# companion_revc.net
KiCad netlist of a schematic drawn in EAGLE
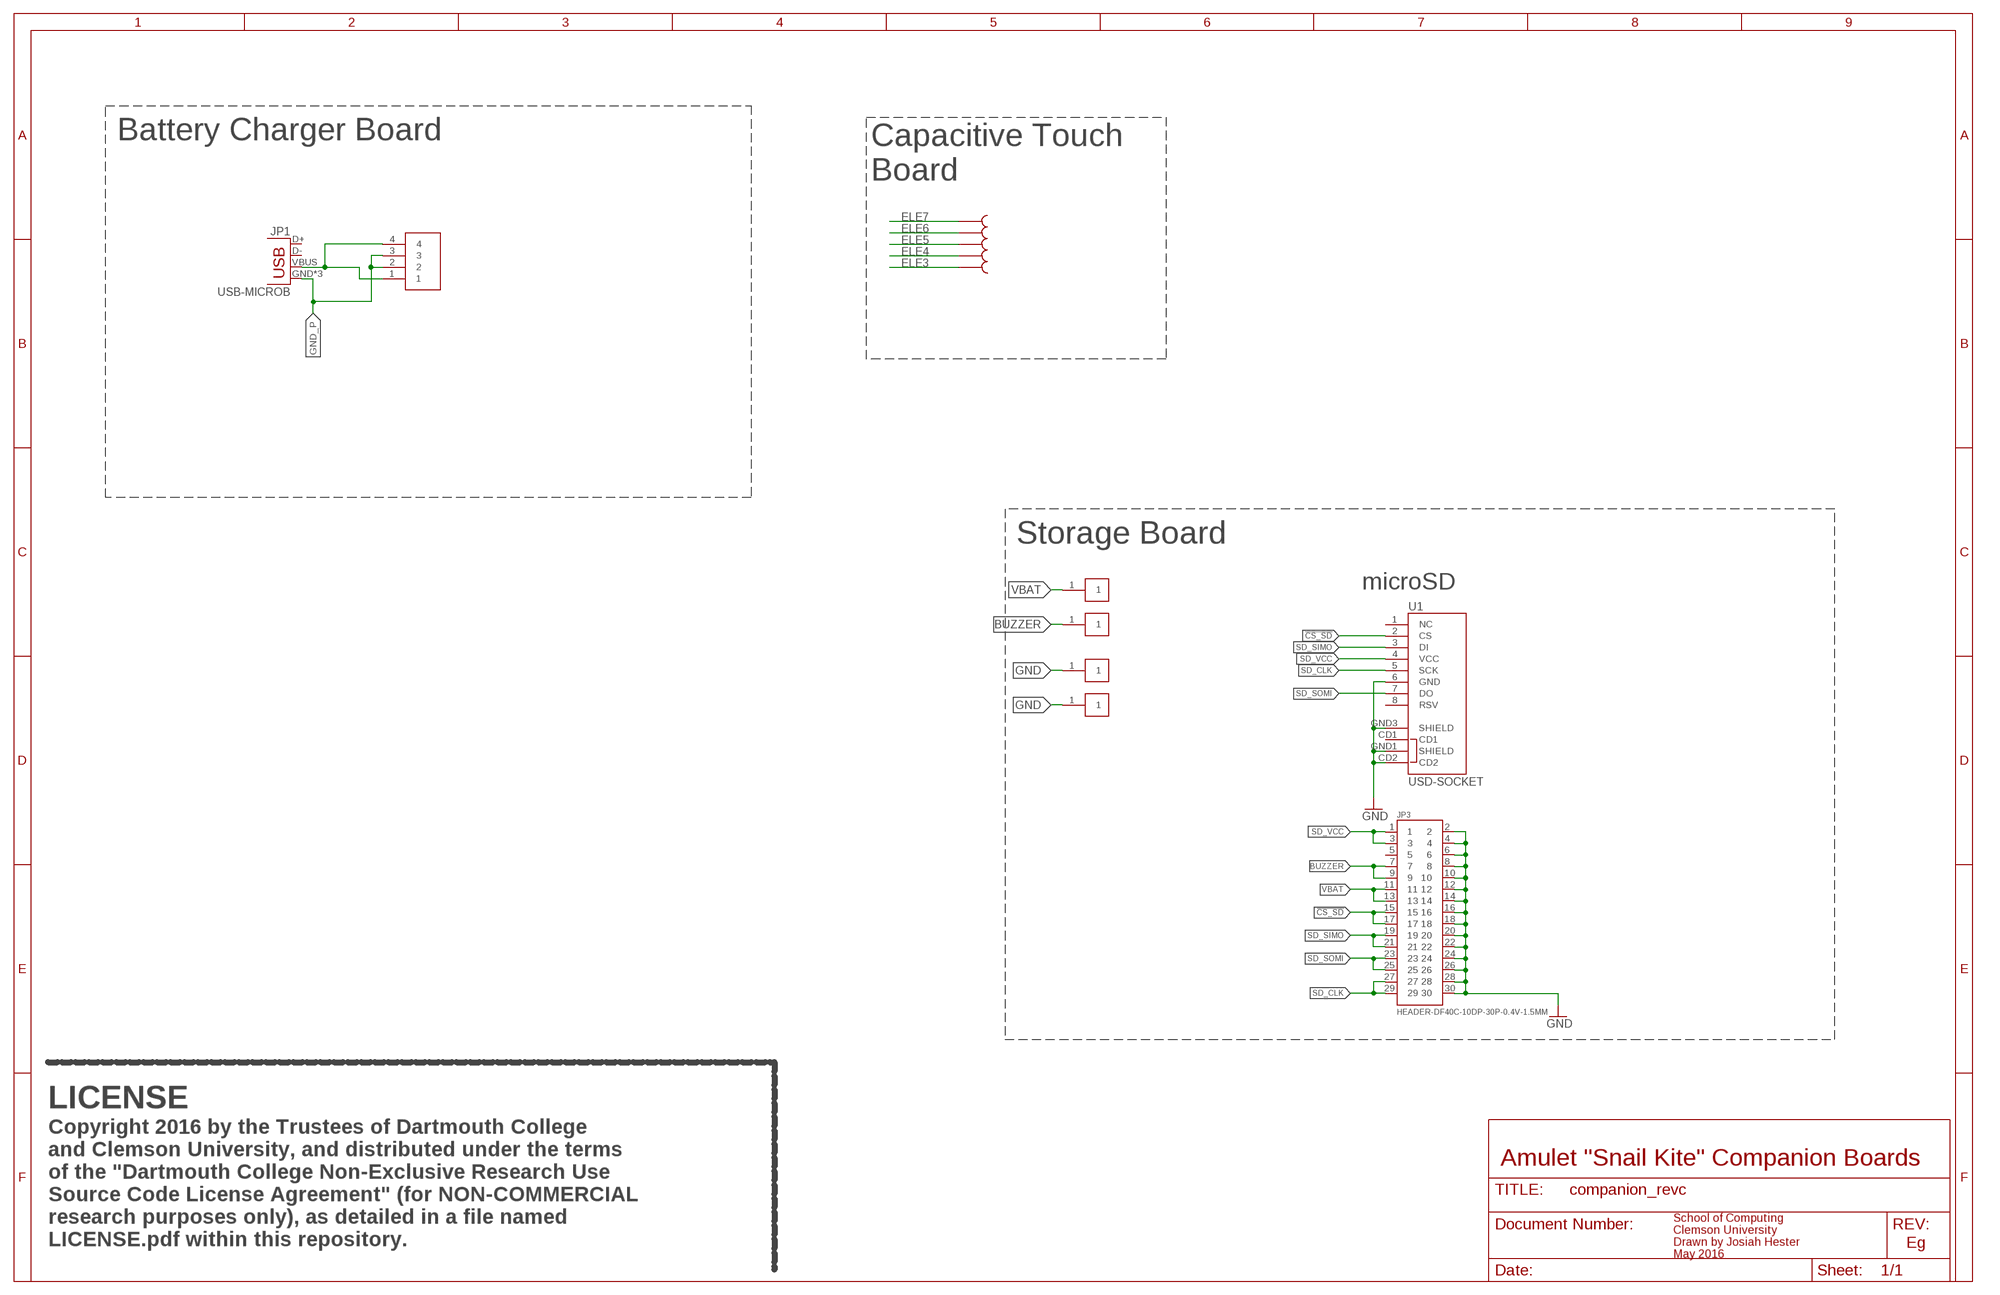
[diagram p0: schematic, sheet 1]

(export (version "E")
  (design (tool "Eeschema 10.0.6"))
  (components
    (comp (ref "JP1")
      (value "USB-MICROB")
      (footprint "eagle-import:USB-MICROB")
      (libsource (lib "eagle-import") (part "USB-MICROB"))
    )
    (comp (ref "JP3")
      (value "HEADER-DF40C-10DP-30P-0.4V-1.5MM")
      (footprint "eagle-import:HEADER-DF40-30")
      (libsource (lib "eagle-import") (part "HEADER-DF40C-10DP-30P-0.4V-1.5MM"))
    )
    (comp (ref "U$1")
      (value "CTPAD")
      (footprint "eagle-import:CTPAD")
      (libsource (lib "eagle-import") (part "CTPAD"))
    )
    (comp (ref "U$2")
      (value "CTPAD")
      (footprint "eagle-import:CTPAD")
      (libsource (lib "eagle-import") (part "CTPAD"))
    )
    (comp (ref "U$3")
      (value "CTPAD")
      (footprint "eagle-import:CTPAD")
      (libsource (lib "eagle-import") (part "CTPAD"))
    )
    (comp (ref "U$4")
      (value "CTPAD")
      (footprint "eagle-import:CTPAD")
      (libsource (lib "eagle-import") (part "CTPAD"))
    )
    (comp (ref "U$5")
      (value "CTPAD")
      (footprint "eagle-import:CTPAD")
      (libsource (lib "eagle-import") (part "CTPAD"))
    )
    (comp (ref "U$6")
      (value "1PAD")
      (footprint "eagle-import:5X23MM_PAD")
      (libsource (lib "eagle-import") (part "1PAD"))
    )
    (comp (ref "U$7")
      (value "1PAD")
      (footprint "eagle-import:5X23MM_PAD")
      (libsource (lib "eagle-import") (part "1PAD"))
    )
    (comp (ref "U$8")
      (value "1PAD")
      (footprint "eagle-import:5X23MM_PAD")
      (libsource (lib "eagle-import") (part "1PAD"))
    )
    (comp (ref "U$9")
      (value "1PAD")
      (footprint "eagle-import:5X23MM_PAD")
      (libsource (lib "eagle-import") (part "1PAD"))
    )
    (comp (ref "U$10")
      (value "1.27MM-MILLMAX")
      (footprint "eagle-import:1X03-1.27MM")
      (libsource (lib "eagle-import") (part "1.27MM-MILLMAX"))
    )
    (comp (ref "U1")
      (value "USD-SOCKET")
      (footprint "eagle-import:MICROSD_1_1")
      (libsource (lib "eagle-import") (part "USD-SOCKET"))
    )
  )
  (nets
    (net (code "1") (name "/ELE3") (class "Default")
      (node (ref "U$5") (pin "P$1") (pinfunction "P$1_P$1") (pintype "bidirectional"))
    )
    (net (code "2") (name "/ELE4") (class "Default")
      (node (ref "U$4") (pin "P$1") (pinfunction "P$1_P$1") (pintype "bidirectional"))
    )
    (net (code "3") (name "/ELE5") (class "Default")
      (node (ref "U$3") (pin "P$1") (pinfunction "P$1_P$1") (pintype "bidirectional"))
    )
    (net (code "4") (name "/ELE6") (class "Default")
      (node (ref "U$2") (pin "P$1") (pinfunction "P$1_P$1") (pintype "bidirectional"))
    )
    (net (code "5") (name "/ELE7") (class "Default")
      (node (ref "U$1") (pin "P$1") (pinfunction "P$1_P$1") (pintype "bidirectional"))
    )
    (net (code "6") (name "/~{CS_SD}") (class "Default")
      (node (ref "JP3") (pin "15") (pinfunction "15_15") (pintype "bidirectional"))
      (node (ref "JP3") (pin "17") (pinfunction "17_17") (pintype "bidirectional"))
      (node (ref "U1") (pin "2") (pinfunction "CS_2") (pintype "bidirectional"))
    )
    (net (code "7") (name "BUZZER") (class "Default")
      (node (ref "JP3") (pin "7") (pinfunction "7_7") (pintype "bidirectional"))
      (node (ref "JP3") (pin "9") (pinfunction "9_9") (pintype "bidirectional"))
      (node (ref "U$7") (pin "1") (pinfunction "1_1") (pintype "bidirectional"))
    )
    (net (code "8") (name "GND") (class "Default")
      (node (ref "JP3") (pin "10") (pinfunction "10_10") (pintype "bidirectional"))
      (node (ref "JP3") (pin "12") (pinfunction "12_12") (pintype "bidirectional"))
      (node (ref "JP3") (pin "14") (pinfunction "14_14") (pintype "bidirectional"))
      (node (ref "JP3") (pin "16") (pinfunction "16_16") (pintype "bidirectional"))
      (node (ref "JP3") (pin "18") (pinfunction "18_18") (pintype "bidirectional"))
      (node (ref "JP3") (pin "2") (pinfunction "2_2") (pintype "bidirectional"))
      (node (ref "JP3") (pin "20") (pinfunction "20_20") (pintype "bidirectional"))
      (node (ref "JP3") (pin "22") (pinfunction "22_22") (pintype "bidirectional"))
      (node (ref "JP3") (pin "24") (pinfunction "24_24") (pintype "bidirectional"))
      (node (ref "JP3") (pin "26") (pinfunction "26_26") (pintype "bidirectional"))
      (node (ref "JP3") (pin "28") (pinfunction "28_28") (pintype "bidirectional"))
      (node (ref "JP3") (pin "30") (pinfunction "30_30") (pintype "bidirectional"))
      (node (ref "JP3") (pin "4") (pinfunction "4_4") (pintype "bidirectional"))
      (node (ref "JP3") (pin "6") (pinfunction "6_6") (pintype "bidirectional"))
      (node (ref "JP3") (pin "8") (pinfunction "8_8") (pintype "bidirectional"))
      (node (ref "U$8") (pin "1") (pinfunction "1_1") (pintype "bidirectional"))
      (node (ref "U$9") (pin "1") (pinfunction "1_1") (pintype "bidirectional"))
      (node (ref "U1") (pin "6") (pinfunction "GND_6") (pintype "bidirectional"))
      (node (ref "U1") (pin "CD2") (pinfunction "CD2_CD2") (pintype "bidirectional"))
      (node (ref "U1") (pin "GND1") (pinfunction "SHIELD_GND1") (pintype "bidirectional"))
      (node (ref "U1") (pin "GND3") (pinfunction "SHIELD_GND3") (pintype "bidirectional"))
    )
    (net (code "9") (name "GND_P") (class "Default")
      (node (ref "JP1") (pin "GND") (pinfunction "GND_GND") (pintype "bidirectional"))
      (node (ref "JP1") (pin "MT1") (pinfunction "GND_MT1") (pintype "bidirectional"))
      (node (ref "JP1") (pin "MT2") (pinfunction "GND_MT2") (pintype "bidirectional"))
      (node (ref "U$10") (pin "2") (pinfunction "2_2") (pintype "bidirectional"))
      (node (ref "U$10") (pin "3") (pinfunction "3_3") (pintype "bidirectional"))
    )
    (net (code "10") (name "Net-(JP1-PadVBUS)") (class "Default")
      (node (ref "JP1") (pin "VBUS") (pinfunction "VBUS_VBUS") (pintype "bidirectional"))
      (node (ref "U$10") (pin "1") (pinfunction "1_1") (pintype "bidirectional"))
      (node (ref "U$10") (pin "4") (pinfunction "4_4") (pintype "bidirectional"))
    )
    (net (code "11") (name "SD_CLK") (class "Default")
      (node (ref "JP3") (pin "27") (pinfunction "27_27") (pintype "bidirectional"))
      (node (ref "JP3") (pin "29") (pinfunction "29_29") (pintype "bidirectional"))
      (node (ref "U1") (pin "5") (pinfunction "SCK_5") (pintype "bidirectional"))
    )
    (net (code "12") (name "SD_SIMO") (class "Default")
      (node (ref "JP3") (pin "19") (pinfunction "19_19") (pintype "bidirectional"))
      (node (ref "JP3") (pin "21") (pinfunction "21_21") (pintype "bidirectional"))
      (node (ref "U1") (pin "3") (pinfunction "DI_3") (pintype "bidirectional"))
    )
    (net (code "13") (name "SD_SOMI") (class "Default")
      (node (ref "JP3") (pin "23") (pinfunction "23_23") (pintype "bidirectional"))
      (node (ref "JP3") (pin "25") (pinfunction "25_25") (pintype "bidirectional"))
      (node (ref "U1") (pin "7") (pinfunction "DO_7") (pintype "bidirectional"))
    )
    (net (code "14") (name "SD_VCC") (class "Default")
      (node (ref "JP3") (pin "1") (pinfunction "1_1") (pintype "bidirectional"))
      (node (ref "JP3") (pin "3") (pinfunction "3_3") (pintype "bidirectional"))
      (node (ref "U1") (pin "4") (pinfunction "VCC_4") (pintype "bidirectional"))
    )
    (net (code "15") (name "VBAT") (class "Default")
      (node (ref "JP3") (pin "11") (pinfunction "11_11") (pintype "bidirectional"))
      (node (ref "JP3") (pin "13") (pinfunction "13_13") (pintype "bidirectional"))
      (node (ref "U$6") (pin "1") (pinfunction "1_1") (pintype "bidirectional"))
    )
    (net (code "16") (name "unconnected-(JP1-PadD+)") (class "Default")
      (node (ref "JP1") (pin "D+") (pinfunction "D+_D+") (pintype "bidirectional"))
    )
    (net (code "17") (name "unconnected-(JP1-PadD-)") (class "Default")
      (node (ref "JP1") (pin "D-") (pinfunction "D-_D-") (pintype "bidirectional"))
    )
    (net (code "18") (name "unconnected-(JP3-Pad5)") (class "Default")
      (node (ref "JP3") (pin "5") (pinfunction "5_5") (pintype "bidirectional"))
    )
    (net (code "19") (name "unconnected-(U1-NC-Pad1)") (class "Default")
      (node (ref "U1") (pin "1") (pinfunction "NC_1") (pintype "bidirectional"))
    )
    (net (code "20") (name "unconnected-(U1-PadCD1)") (class "Default")
      (node (ref "U1") (pin "CD1") (pinfunction "CD1_CD1") (pintype "bidirectional"))
    )
    (net (code "21") (name "unconnected-(U1-RSV-Pad8)") (class "Default")
      (node (ref "U1") (pin "8") (pinfunction "RSV_8") (pintype "bidirectional"))
    )
  )
)
